# Joystick_Module_A.net
KiCad netlist of a schematic drawn in EAGLE
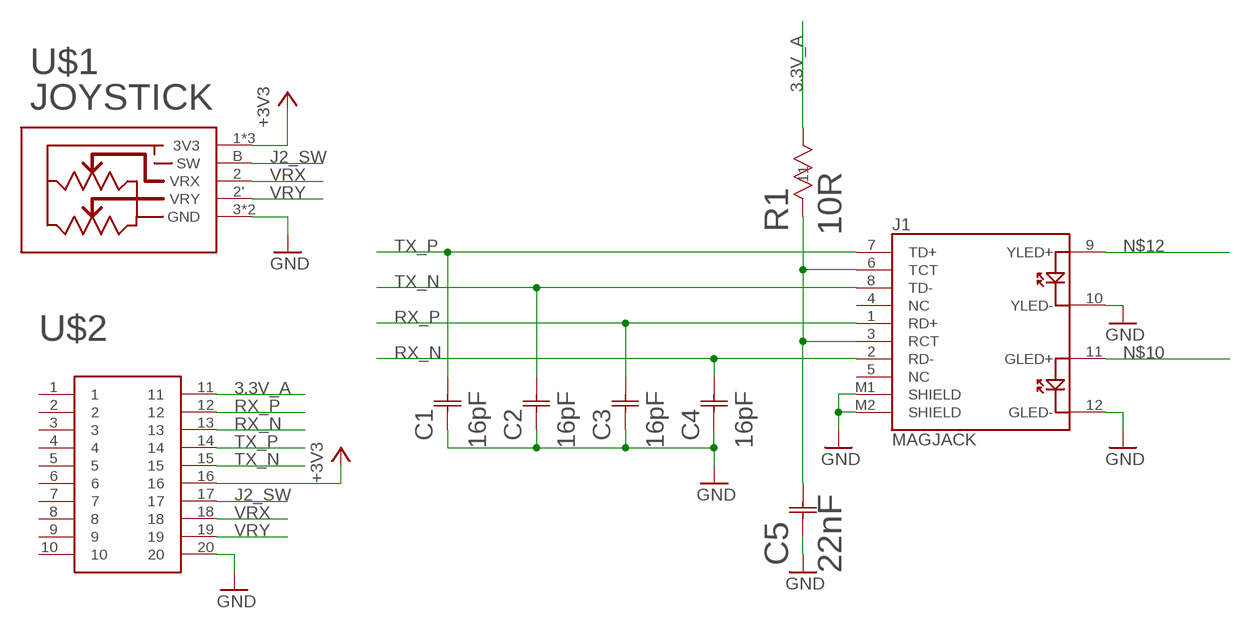
[diagram p0: schematic, sheet 1]

(export (version "E")
  (design (tool "Eeschema 10.0.6"))
  (components
    (comp (ref "C1")
      (value "16pF")
      (footprint "eagle-import:G-155-M")
      (fields (field (name "MANUFACTURER_PART_NUMBER") "GRM1555C1H160JA01D"))
      (libsource (lib "eagle-import") (part "GRM1555C1H160JA01DG-155-M"))
    )
    (comp (ref "C2")
      (value "16pF")
      (footprint "eagle-import:G-155-M")
      (fields (field (name "MANUFACTURER_PART_NUMBER") "GRM1555C1H160JA01D"))
      (libsource (lib "eagle-import") (part "GRM1555C1H160JA01DG-155-M"))
    )
    (comp (ref "C3")
      (value "16pF")
      (footprint "eagle-import:G-155-M")
      (fields (field (name "MANUFACTURER_PART_NUMBER") "GRM1555C1H160JA01D"))
      (libsource (lib "eagle-import") (part "GRM1555C1H160JA01DG-155-M"))
    )
    (comp (ref "C4")
      (value "16pF")
      (footprint "eagle-import:G-155-M")
      (fields (field (name "MANUFACTURER_PART_NUMBER") "GRM1555C1H160JA01D"))
      (libsource (lib "eagle-import") (part "GRM1555C1H160JA01DG-155-M"))
    )
    (comp (ref "C5")
      (value "22nF")
      (footprint "eagle-import:G-155-M")
      (fields (field (name "MANUFACTURER_PART_NUMBER") "GRM155R71H223KA12D"))
      (libsource (lib "eagle-import") (part "GRM155R71H223KA12DG-155-M"))
    )
    (comp (ref "J1")
      (value "MAGJACK")
      (footprint "eagle-import:MAGJACK")
      (libsource (lib "eagle-import") (part "MAGJACK"))
    )
    (comp (ref "R1")
      (value "10R")
      (footprint "eagle-import:STA_RNCP0805-M")
      (fields
        (field (name "MANUFACTURER_PART_NUMBER") "RNCP0805FTD10R0")
        (field (name "COPYRIGHT") "Copyright C 2015 Accelerated Designs. All rights reserved")
      )
      (libsource (lib "eagle-import") (part "RNCP0805FTD10R0STA_RNCP0805-M"))
    )
    (comp (ref "U$1")
      (value "JOYSTICK\"")
      (footprint "eagle-import:JOYSTICK")
      (libsource (lib "eagle-import") (part "JOYSTICK{dblquote}"))
    )
    (comp (ref "U$2")
      (value "EDGE_CONNECTOR_20POS_CONTACTS")
      (footprint "eagle-import:EDGE_CONNECTOR_20POS_CONTACTS")
      (libsource (lib "eagle-import") (part "EDGE_CONNECTOR_20POS_CONTACTS"))
    )
  )
  (nets
    (net (code "1") (name "+3V3") (class "Default")
      (node (ref "U$1") (pin "1") (pinfunction "3V3_1") (pintype "power_in"))
      (node (ref "U$1") (pin "1'") (pinfunction "3V3_1'") (pintype "power_in"))
      (node (ref "U$1") (pin "A") (pinfunction "3V3_A") (pintype "power_in"))
      (node (ref "U$2") (pin "16") (pinfunction "16_16") (pintype "bidirectional"))
    )
    (net (code "2") (name "/3.3V_A") (class "Default")
      (node (ref "R1") (pin "2") (pinfunction "22_2") (pintype "passive"))
      (node (ref "U$2") (pin "11") (pinfunction "11_11") (pintype "bidirectional"))
    )
    (net (code "3") (name "/J2_SW") (class "Default")
      (node (ref "U$1") (pin "B") (pinfunction "SW_B") (pintype "bidirectional"))
      (node (ref "U$2") (pin "17") (pinfunction "17_17") (pintype "bidirectional"))
    )
    (net (code "4") (name "/N$10") (class "Default")
      (node (ref "J1") (pin "11") (pinfunction "GLED+_11") (pintype "bidirectional"))
    )
    (net (code "5") (name "/N$12") (class "Default")
      (node (ref "J1") (pin "9") (pinfunction "YLED+_9") (pintype "bidirectional"))
    )
    (net (code "6") (name "/RX_N") (class "Default")
      (node (ref "C4") (pin "2") (pinfunction "22_2") (pintype "passive"))
      (node (ref "J1") (pin "2") (pinfunction "RD-_2") (pintype "bidirectional"))
      (node (ref "U$2") (pin "13") (pinfunction "13_13") (pintype "bidirectional"))
    )
    (net (code "7") (name "/RX_P") (class "Default")
      (node (ref "C3") (pin "2") (pinfunction "22_2") (pintype "passive"))
      (node (ref "J1") (pin "1") (pinfunction "RD+_1") (pintype "bidirectional"))
      (node (ref "U$2") (pin "12") (pinfunction "12_12") (pintype "bidirectional"))
    )
    (net (code "8") (name "/TX_N") (class "Default")
      (node (ref "C2") (pin "2") (pinfunction "22_2") (pintype "passive"))
      (node (ref "J1") (pin "8") (pinfunction "TD-_8") (pintype "bidirectional"))
      (node (ref "U$2") (pin "15") (pinfunction "15_15") (pintype "bidirectional"))
    )
    (net (code "9") (name "/TX_P") (class "Default")
      (node (ref "C1") (pin "2") (pinfunction "22_2") (pintype "passive"))
      (node (ref "J1") (pin "7") (pinfunction "TD+_7") (pintype "bidirectional"))
      (node (ref "U$2") (pin "14") (pinfunction "14_14") (pintype "bidirectional"))
    )
    (net (code "10") (name "/VRX") (class "Default")
      (node (ref "U$1") (pin "2") (pinfunction "VRX_2") (pintype "bidirectional"))
      (node (ref "U$2") (pin "18") (pinfunction "18_18") (pintype "bidirectional"))
    )
    (net (code "11") (name "/VRY") (class "Default")
      (node (ref "U$1") (pin "2'") (pinfunction "VRY_2'") (pintype "bidirectional"))
      (node (ref "U$2") (pin "19") (pinfunction "19_19") (pintype "bidirectional"))
    )
    (net (code "12") (name "GND") (class "Default")
      (node (ref "C1") (pin "1") (pinfunction "11_1") (pintype "passive"))
      (node (ref "C2") (pin "1") (pinfunction "11_1") (pintype "passive"))
      (node (ref "C3") (pin "1") (pinfunction "11_1") (pintype "passive"))
      (node (ref "C4") (pin "1") (pinfunction "11_1") (pintype "passive"))
      (node (ref "C5") (pin "1") (pinfunction "11_1") (pintype "passive"))
      (node (ref "J1") (pin "10") (pinfunction "YLED-_10") (pintype "bidirectional"))
      (node (ref "J1") (pin "12") (pinfunction "GLED-_12") (pintype "bidirectional"))
      (node (ref "J1") (pin "M1") (pinfunction "SHIELD_M1") (pintype "bidirectional"))
      (node (ref "J1") (pin "M2") (pinfunction "SHIELD_M2") (pintype "bidirectional"))
      (node (ref "U$1") (pin "3") (pinfunction "GND_3") (pintype "power_in"))
      (node (ref "U$1") (pin "3'") (pinfunction "GND_3'") (pintype "power_in"))
      (node (ref "U$2") (pin "20") (pinfunction "20_20") (pintype "bidirectional"))
    )
    (net (code "13") (name "Net-(C5-22)") (class "Default")
      (node (ref "C5") (pin "2") (pinfunction "22_2") (pintype "passive"))
      (node (ref "J1") (pin "3") (pinfunction "RCT_3") (pintype "bidirectional"))
      (node (ref "J1") (pin "6") (pinfunction "TCT_6") (pintype "bidirectional"))
      (node (ref "R1") (pin "1") (pinfunction "11_1") (pintype "passive"))
    )
    (net (code "14") (name "unconnected-(J1-NC-Pad4)") (class "Default")
      (node (ref "J1") (pin "4") (pinfunction "NC_4") (pintype "bidirectional"))
    )
    (net (code "15") (name "unconnected-(J1-NC-Pad5)") (class "Default")
      (node (ref "J1") (pin "5") (pinfunction "NC_5") (pintype "bidirectional"))
    )
    (net (code "16") (name "unconnected-(U$2-Pad1)") (class "Default")
      (node (ref "U$2") (pin "1") (pinfunction "1_1") (pintype "bidirectional"))
    )
    (net (code "17") (name "unconnected-(U$2-Pad2)") (class "Default")
      (node (ref "U$2") (pin "2") (pinfunction "2_2") (pintype "bidirectional"))
    )
    (net (code "18") (name "unconnected-(U$2-Pad3)") (class "Default")
      (node (ref "U$2") (pin "3") (pinfunction "3_3") (pintype "bidirectional"))
    )
    (net (code "19") (name "unconnected-(U$2-Pad4)") (class "Default")
      (node (ref "U$2") (pin "4") (pinfunction "4_4") (pintype "bidirectional"))
    )
    (net (code "20") (name "unconnected-(U$2-Pad5)") (class "Default")
      (node (ref "U$2") (pin "5") (pinfunction "5_5") (pintype "bidirectional"))
    )
    (net (code "21") (name "unconnected-(U$2-Pad6)") (class "Default")
      (node (ref "U$2") (pin "6") (pinfunction "6_6") (pintype "bidirectional"))
    )
    (net (code "22") (name "unconnected-(U$2-Pad7)") (class "Default")
      (node (ref "U$2") (pin "7") (pinfunction "7_7") (pintype "bidirectional"))
    )
    (net (code "23") (name "unconnected-(U$2-Pad8)") (class "Default")
      (node (ref "U$2") (pin "8") (pinfunction "8_8") (pintype "bidirectional"))
    )
    (net (code "24") (name "unconnected-(U$2-Pad9)") (class "Default")
      (node (ref "U$2") (pin "9") (pinfunction "9_9") (pintype "bidirectional"))
    )
    (net (code "25") (name "unconnected-(U$2-Pad10)") (class "Default")
      (node (ref "U$2") (pin "10") (pinfunction "10_10") (pintype "bidirectional"))
    )
  )
)
